# M-Toggle.net
KiCad netlist of a schematic drawn in EAGLE
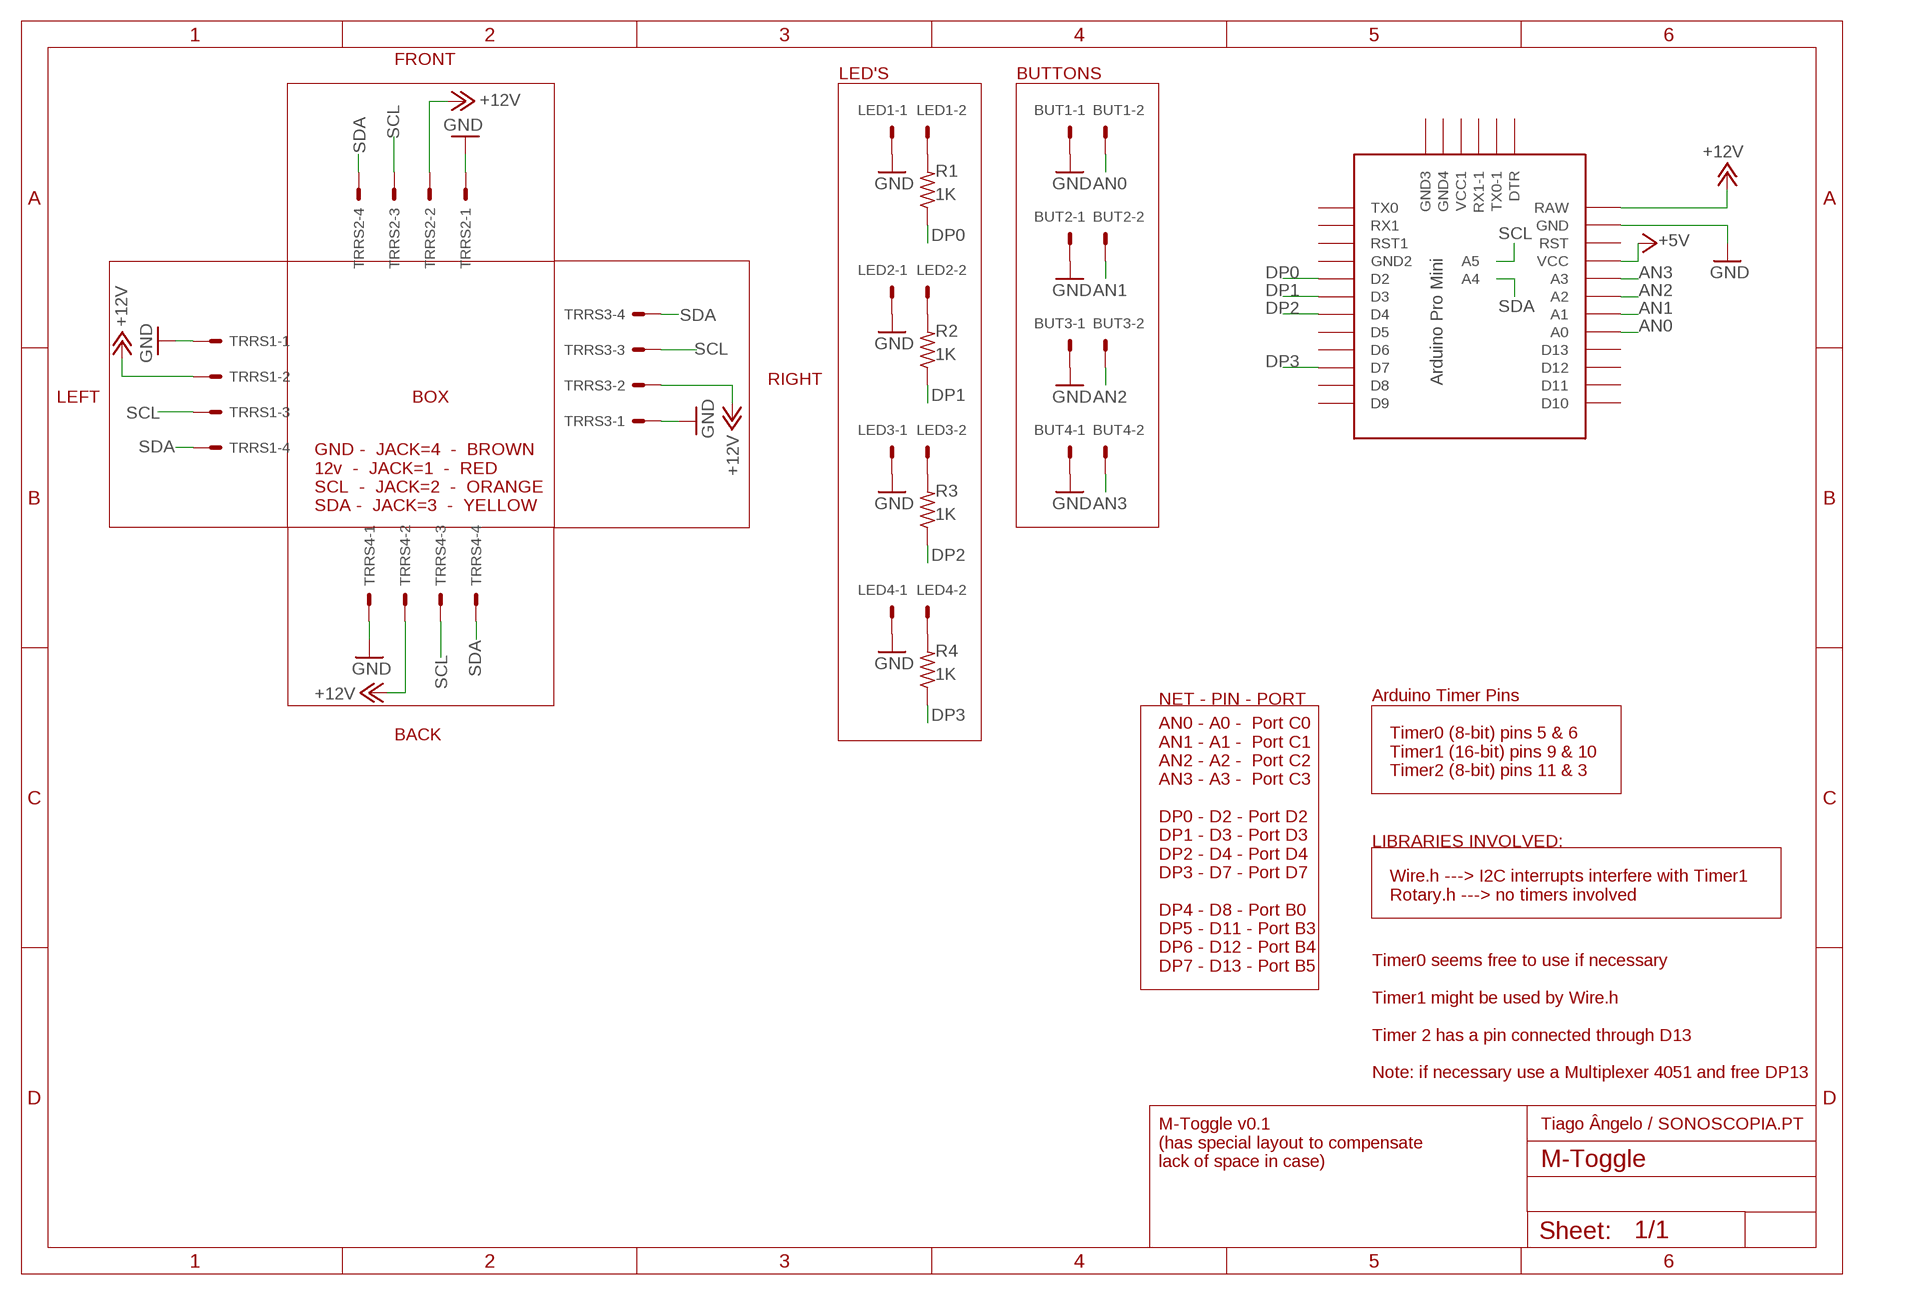
[diagram p0: schematic, sheet 1]

(export (version "E")
  (design (tool "Eeschema 10.0.6"))
  (components
    (comp (ref "BUT1")
      (value "22-27-2021-02")
      (footprint "eagle-import:6410-02")
      (libsource (lib "eagle-import") (part "22-?-0227-2021"))
    )
    (comp (ref "BUT2")
      (value "22-27-2021-02")
      (footprint "eagle-import:6410-02")
      (libsource (lib "eagle-import") (part "22-?-0227-2021"))
    )
    (comp (ref "BUT3")
      (value "22-27-2021-02")
      (footprint "eagle-import:6410-02")
      (libsource (lib "eagle-import") (part "22-?-0227-2021"))
    )
    (comp (ref "BUT4")
      (value "22-27-2021-02")
      (footprint "eagle-import:6410-02")
      (libsource (lib "eagle-import") (part "22-?-0227-2021"))
    )
    (comp (ref "LED1")
      (value "22-27-2021-02")
      (footprint "eagle-import:6410-02")
      (libsource (lib "eagle-import") (part "22-?-0227-2021"))
    )
    (comp (ref "LED2")
      (value "22-27-2021-02")
      (footprint "eagle-import:6410-02")
      (libsource (lib "eagle-import") (part "22-?-0227-2021"))
    )
    (comp (ref "LED3")
      (value "22-27-2021-02")
      (footprint "eagle-import:6410-02")
      (libsource (lib "eagle-import") (part "22-?-0227-2021"))
    )
    (comp (ref "LED4")
      (value "22-27-2021-02")
      (footprint "eagle-import:6410-02")
      (libsource (lib "eagle-import") (part "22-?-0227-2021"))
    )
    (comp (ref "R1")
      (value "1K")
      (footprint "eagle-import:0204_7")
      (libsource (lib "eagle-import") (part "R-US_0204/7"))
    )
    (comp (ref "R2")
      (value "1K")
      (footprint "eagle-import:0204_7")
      (libsource (lib "eagle-import") (part "R-US_0204/7"))
    )
    (comp (ref "R3")
      (value "1K")
      (footprint "eagle-import:0204_7")
      (libsource (lib "eagle-import") (part "R-US_0204/7"))
    )
    (comp (ref "R4")
      (value "1K")
      (footprint "eagle-import:0204_7")
      (libsource (lib "eagle-import") (part "R-US_0204/7"))
    )
    (comp (ref "TRRS1")
      (value "22-27-2041-04")
      (footprint "eagle-import:6410-04")
      (libsource (lib "eagle-import") (part "22-?-0427-2041"))
    )
    (comp (ref "TRRS2")
      (value "22-27-2041-04")
      (footprint "eagle-import:6410-04")
      (libsource (lib "eagle-import") (part "22-?-0427-2041"))
    )
    (comp (ref "TRRS3")
      (value "22-27-2041-04")
      (footprint "eagle-import:6410-04")
      (libsource (lib "eagle-import") (part "22-?-0427-2041"))
    )
    (comp (ref "TRRS4")
      (value "22-27-2041-04")
      (footprint "eagle-import:6410-04")
      (libsource (lib "eagle-import") (part "22-?-0427-2041"))
    )
    (comp (ref "U$1")
      (value "PRO-MINI-2")
      (footprint "eagle-import:PRO-MINI-2")
      (libsource (lib "eagle-import") (part "PRO-MINI-2"))
    )
  )
  (nets
    (net (code "1") (name "+5V") (class "Default")
      (node (ref "U$1") (pin "VCC") (pinfunction "VCC_VCC") (pintype "bidirectional"))
    )
    (net (code "2") (name "+12V") (class "Default")
      (node (ref "TRRS1") (pin "2") (pinfunction "S_2") (pintype "passive"))
      (node (ref "TRRS2") (pin "2") (pinfunction "S_2") (pintype "passive"))
      (node (ref "TRRS3") (pin "2") (pinfunction "S_2") (pintype "passive"))
      (node (ref "TRRS4") (pin "2") (pinfunction "S_2") (pintype "passive"))
      (node (ref "U$1") (pin "RAW") (pinfunction "RAW_RAW") (pintype "bidirectional"))
    )
    (net (code "3") (name "/AN0") (class "Default")
      (node (ref "BUT1") (pin "2") (pinfunction "S_2") (pintype "passive"))
      (node (ref "U$1") (pin "A0") (pinfunction "A0_A0") (pintype "bidirectional"))
    )
    (net (code "4") (name "/AN1") (class "Default")
      (node (ref "BUT2") (pin "2") (pinfunction "S_2") (pintype "passive"))
      (node (ref "U$1") (pin "A1") (pinfunction "A1_A1") (pintype "bidirectional"))
    )
    (net (code "5") (name "/AN2") (class "Default")
      (node (ref "BUT3") (pin "2") (pinfunction "S_2") (pintype "passive"))
      (node (ref "U$1") (pin "A2") (pinfunction "A2_A2") (pintype "bidirectional"))
    )
    (net (code "6") (name "/AN3") (class "Default")
      (node (ref "BUT4") (pin "2") (pinfunction "S_2") (pintype "passive"))
      (node (ref "U$1") (pin "A3") (pinfunction "A3_A3") (pintype "bidirectional"))
    )
    (net (code "7") (name "/DP0") (class "Default")
      (node (ref "R1") (pin "1") (pinfunction "1_1") (pintype "passive"))
      (node (ref "U$1") (pin "D2") (pinfunction "D2_D2") (pintype "bidirectional"))
    )
    (net (code "8") (name "/DP1") (class "Default")
      (node (ref "R2") (pin "1") (pinfunction "1_1") (pintype "passive"))
      (node (ref "U$1") (pin "D3") (pinfunction "D3_D3") (pintype "bidirectional"))
    )
    (net (code "9") (name "/DP2") (class "Default")
      (node (ref "R3") (pin "1") (pinfunction "1_1") (pintype "passive"))
      (node (ref "U$1") (pin "D4") (pinfunction "D4_D4") (pintype "bidirectional"))
    )
    (net (code "10") (name "/DP3") (class "Default")
      (node (ref "R4") (pin "1") (pinfunction "1_1") (pintype "passive"))
      (node (ref "U$1") (pin "D7") (pinfunction "D7_D7") (pintype "bidirectional"))
    )
    (net (code "11") (name "/SCL") (class "Default")
      (node (ref "TRRS1") (pin "3") (pinfunction "S_3") (pintype "passive"))
      (node (ref "TRRS2") (pin "3") (pinfunction "S_3") (pintype "passive"))
      (node (ref "TRRS3") (pin "3") (pinfunction "S_3") (pintype "passive"))
      (node (ref "TRRS4") (pin "3") (pinfunction "S_3") (pintype "passive"))
      (node (ref "U$1") (pin "A5") (pinfunction "A5_A5") (pintype "bidirectional"))
    )
    (net (code "12") (name "/SDA") (class "Default")
      (node (ref "TRRS1") (pin "4") (pinfunction "S_4") (pintype "passive"))
      (node (ref "TRRS2") (pin "4") (pinfunction "S_4") (pintype "passive"))
      (node (ref "TRRS3") (pin "4") (pinfunction "S_4") (pintype "passive"))
      (node (ref "TRRS4") (pin "4") (pinfunction "S_4") (pintype "passive"))
      (node (ref "U$1") (pin "A4") (pinfunction "A4_A4") (pintype "bidirectional"))
    )
    (net (code "13") (name "GND") (class "Default")
      (node (ref "BUT1") (pin "1") (pinfunction "S_1") (pintype "passive"))
      (node (ref "BUT2") (pin "1") (pinfunction "S_1") (pintype "passive"))
      (node (ref "BUT3") (pin "1") (pinfunction "S_1") (pintype "passive"))
      (node (ref "BUT4") (pin "1") (pinfunction "S_1") (pintype "passive"))
      (node (ref "LED1") (pin "1") (pinfunction "S_1") (pintype "passive"))
      (node (ref "LED2") (pin "1") (pinfunction "S_1") (pintype "passive"))
      (node (ref "LED3") (pin "1") (pinfunction "S_1") (pintype "passive"))
      (node (ref "LED4") (pin "1") (pinfunction "S_1") (pintype "passive"))
      (node (ref "TRRS1") (pin "1") (pinfunction "S_1") (pintype "passive"))
      (node (ref "TRRS2") (pin "1") (pinfunction "S_1") (pintype "passive"))
      (node (ref "TRRS3") (pin "1") (pinfunction "S_1") (pintype "passive"))
      (node (ref "TRRS4") (pin "1") (pinfunction "S_1") (pintype "passive"))
      (node (ref "U$1") (pin "GND") (pinfunction "GND_GND") (pintype "bidirectional"))
    )
    (net (code "14") (name "Net-(LED1B-S)") (class "Default")
      (node (ref "LED1") (pin "2") (pinfunction "S_2") (pintype "passive"))
      (node (ref "R1") (pin "2") (pinfunction "2_2") (pintype "passive"))
    )
    (net (code "15") (name "Net-(LED2B-S)") (class "Default")
      (node (ref "LED2") (pin "2") (pinfunction "S_2") (pintype "passive"))
      (node (ref "R2") (pin "2") (pinfunction "2_2") (pintype "passive"))
    )
    (net (code "16") (name "Net-(LED3B-S)") (class "Default")
      (node (ref "LED3") (pin "2") (pinfunction "S_2") (pintype "passive"))
      (node (ref "R3") (pin "2") (pinfunction "2_2") (pintype "passive"))
    )
    (net (code "17") (name "Net-(LED4B-S)") (class "Default")
      (node (ref "LED4") (pin "2") (pinfunction "S_2") (pintype "passive"))
      (node (ref "R4") (pin "2") (pinfunction "2_2") (pintype "passive"))
    )
    (net (code "18") (name "unconnected-(U$1-GND2-PadGND1)") (class "Default")
      (node (ref "U$1") (pin "GND1") (pinfunction "GND2_GND1") (pintype "bidirectional"))
    )
    (net (code "19") (name "unconnected-(U$1-GND3-PadGND2)") (class "Default")
      (node (ref "U$1") (pin "GND2") (pinfunction "GND3_GND2") (pintype "bidirectional"))
    )
    (net (code "20") (name "unconnected-(U$1-GND4-PadGND3)") (class "Default")
      (node (ref "U$1") (pin "GND3") (pinfunction "GND4_GND3") (pintype "bidirectional"))
    )
    (net (code "21") (name "unconnected-(U$1-PadD5)") (class "Default")
      (node (ref "U$1") (pin "D5") (pinfunction "D5_D5") (pintype "bidirectional"))
    )
    (net (code "22") (name "unconnected-(U$1-PadD6)") (class "Default")
      (node (ref "U$1") (pin "D6") (pinfunction "D6_D6") (pintype "bidirectional"))
    )
    (net (code "23") (name "unconnected-(U$1-PadD8)") (class "Default")
      (node (ref "U$1") (pin "D8") (pinfunction "D8_D8") (pintype "bidirectional"))
    )
    (net (code "24") (name "unconnected-(U$1-PadD9)") (class "Default")
      (node (ref "U$1") (pin "D9") (pinfunction "D9_D9") (pintype "bidirectional"))
    )
    (net (code "25") (name "unconnected-(U$1-PadD10)") (class "Default")
      (node (ref "U$1") (pin "D10") (pinfunction "D10_D10") (pintype "bidirectional"))
    )
    (net (code "26") (name "unconnected-(U$1-PadD11)") (class "Default")
      (node (ref "U$1") (pin "D11") (pinfunction "D11_D11") (pintype "bidirectional"))
    )
    (net (code "27") (name "unconnected-(U$1-PadD12)") (class "Default")
      (node (ref "U$1") (pin "D12") (pinfunction "D12_D12") (pintype "bidirectional"))
    )
    (net (code "28") (name "unconnected-(U$1-PadD13)") (class "Default")
      (node (ref "U$1") (pin "D13") (pinfunction "D13_D13") (pintype "bidirectional"))
    )
    (net (code "29") (name "unconnected-(U$1-PadDTR)") (class "Default")
      (node (ref "U$1") (pin "DTR") (pinfunction "DTR_DTR") (pintype "bidirectional"))
    )
    (net (code "30") (name "unconnected-(U$1-PadRST)") (class "Default")
      (node (ref "U$1") (pin "RST") (pinfunction "RST_RST") (pintype "bidirectional"))
    )
    (net (code "31") (name "unconnected-(U$1-PadRST1)") (class "Default")
      (node (ref "U$1") (pin "RST1") (pinfunction "RST1_RST1") (pintype "bidirectional"))
    )
    (net (code "32") (name "unconnected-(U$1-PadRX1)") (class "Default")
      (node (ref "U$1") (pin "RX1") (pinfunction "RX1_RX1") (pintype "bidirectional"))
    )
    (net (code "33") (name "unconnected-(U$1-PadRX1-1)") (class "Default")
      (node (ref "U$1") (pin "RX1-1") (pinfunction "RX1-1_RX1-1") (pintype "bidirectional"))
    )
    (net (code "34") (name "unconnected-(U$1-PadTX0)") (class "Default")
      (node (ref "U$1") (pin "TX0") (pinfunction "TX0_TX0") (pintype "bidirectional"))
    )
    (net (code "35") (name "unconnected-(U$1-PadTX0-1)") (class "Default")
      (node (ref "U$1") (pin "TX0-1") (pinfunction "TX0-1_TX0-1") (pintype "bidirectional"))
    )
    (net (code "36") (name "unconnected-(U$1-PadVCC1)") (class "Default")
      (node (ref "U$1") (pin "VCC1") (pinfunction "VCC1_VCC1") (pintype "bidirectional"))
    )
  )
)
